# BinaryClockDisplay.net
KiCad netlist of a schematic drawn in EAGLE
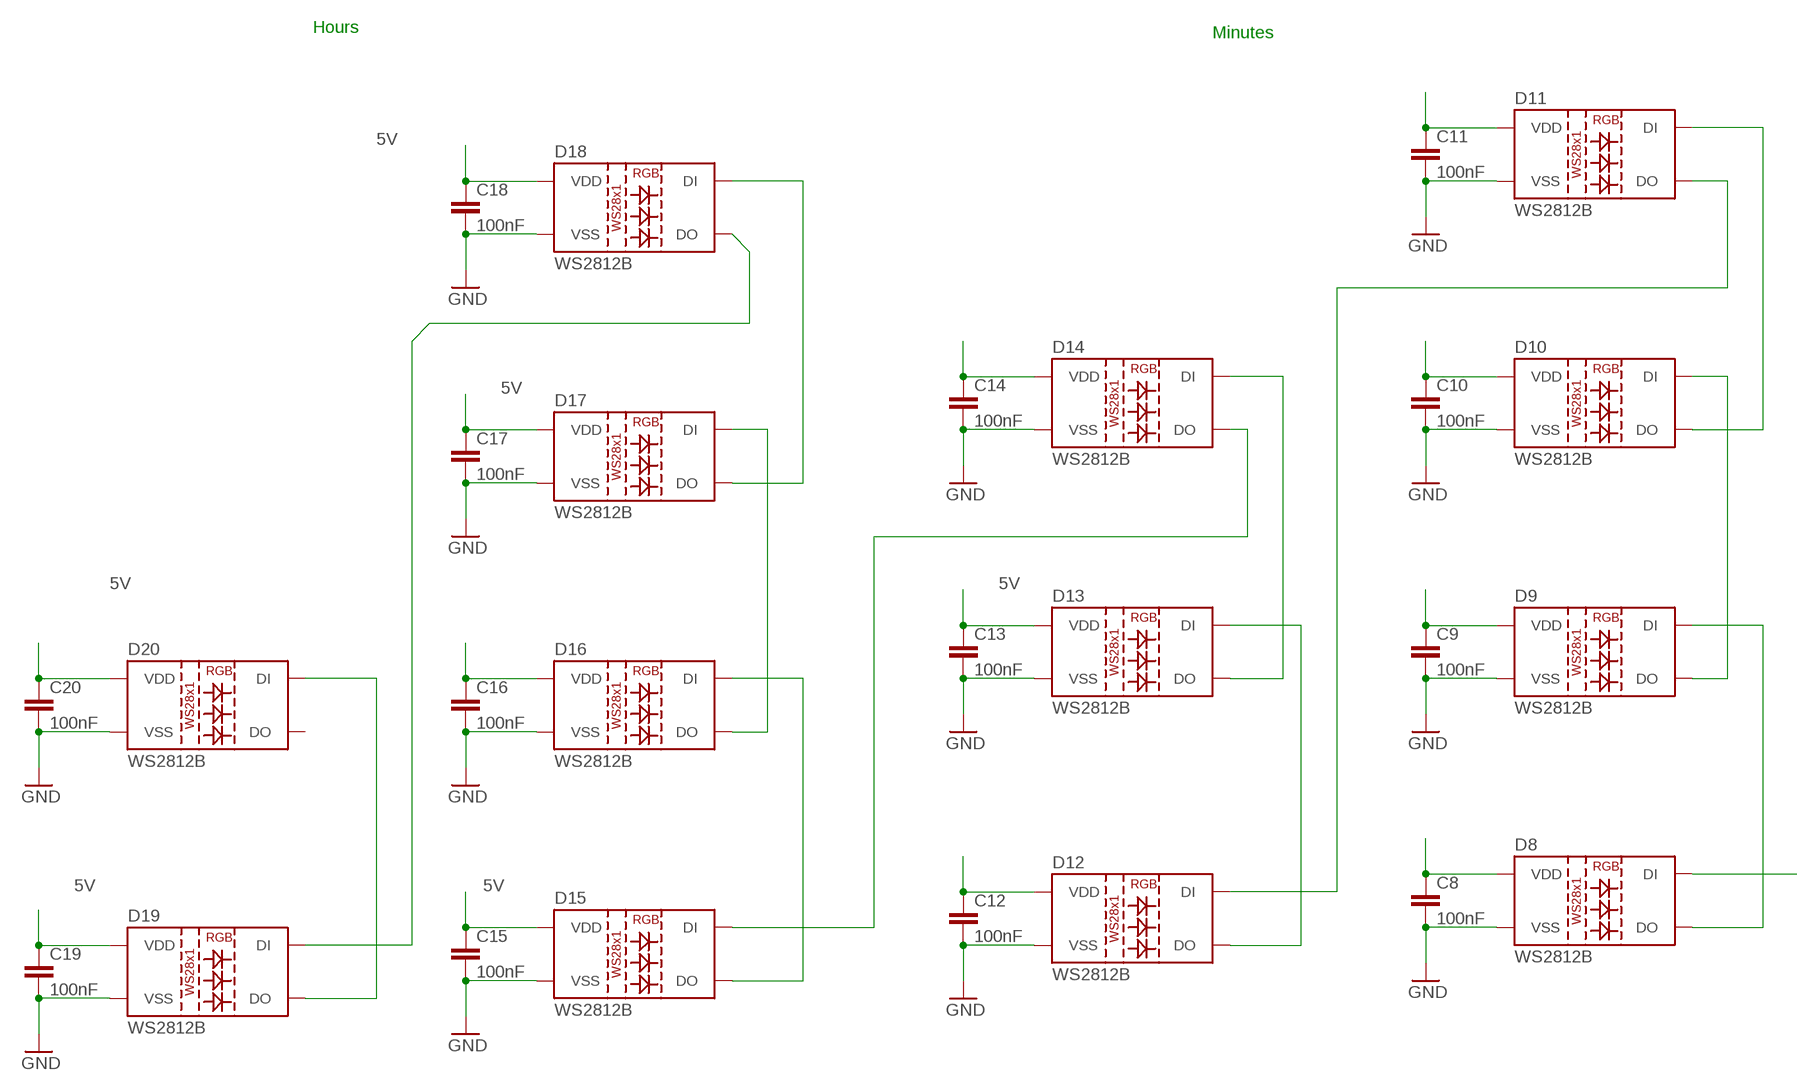
[diagram p0: schematic, sheet 1, part 1 of 2]
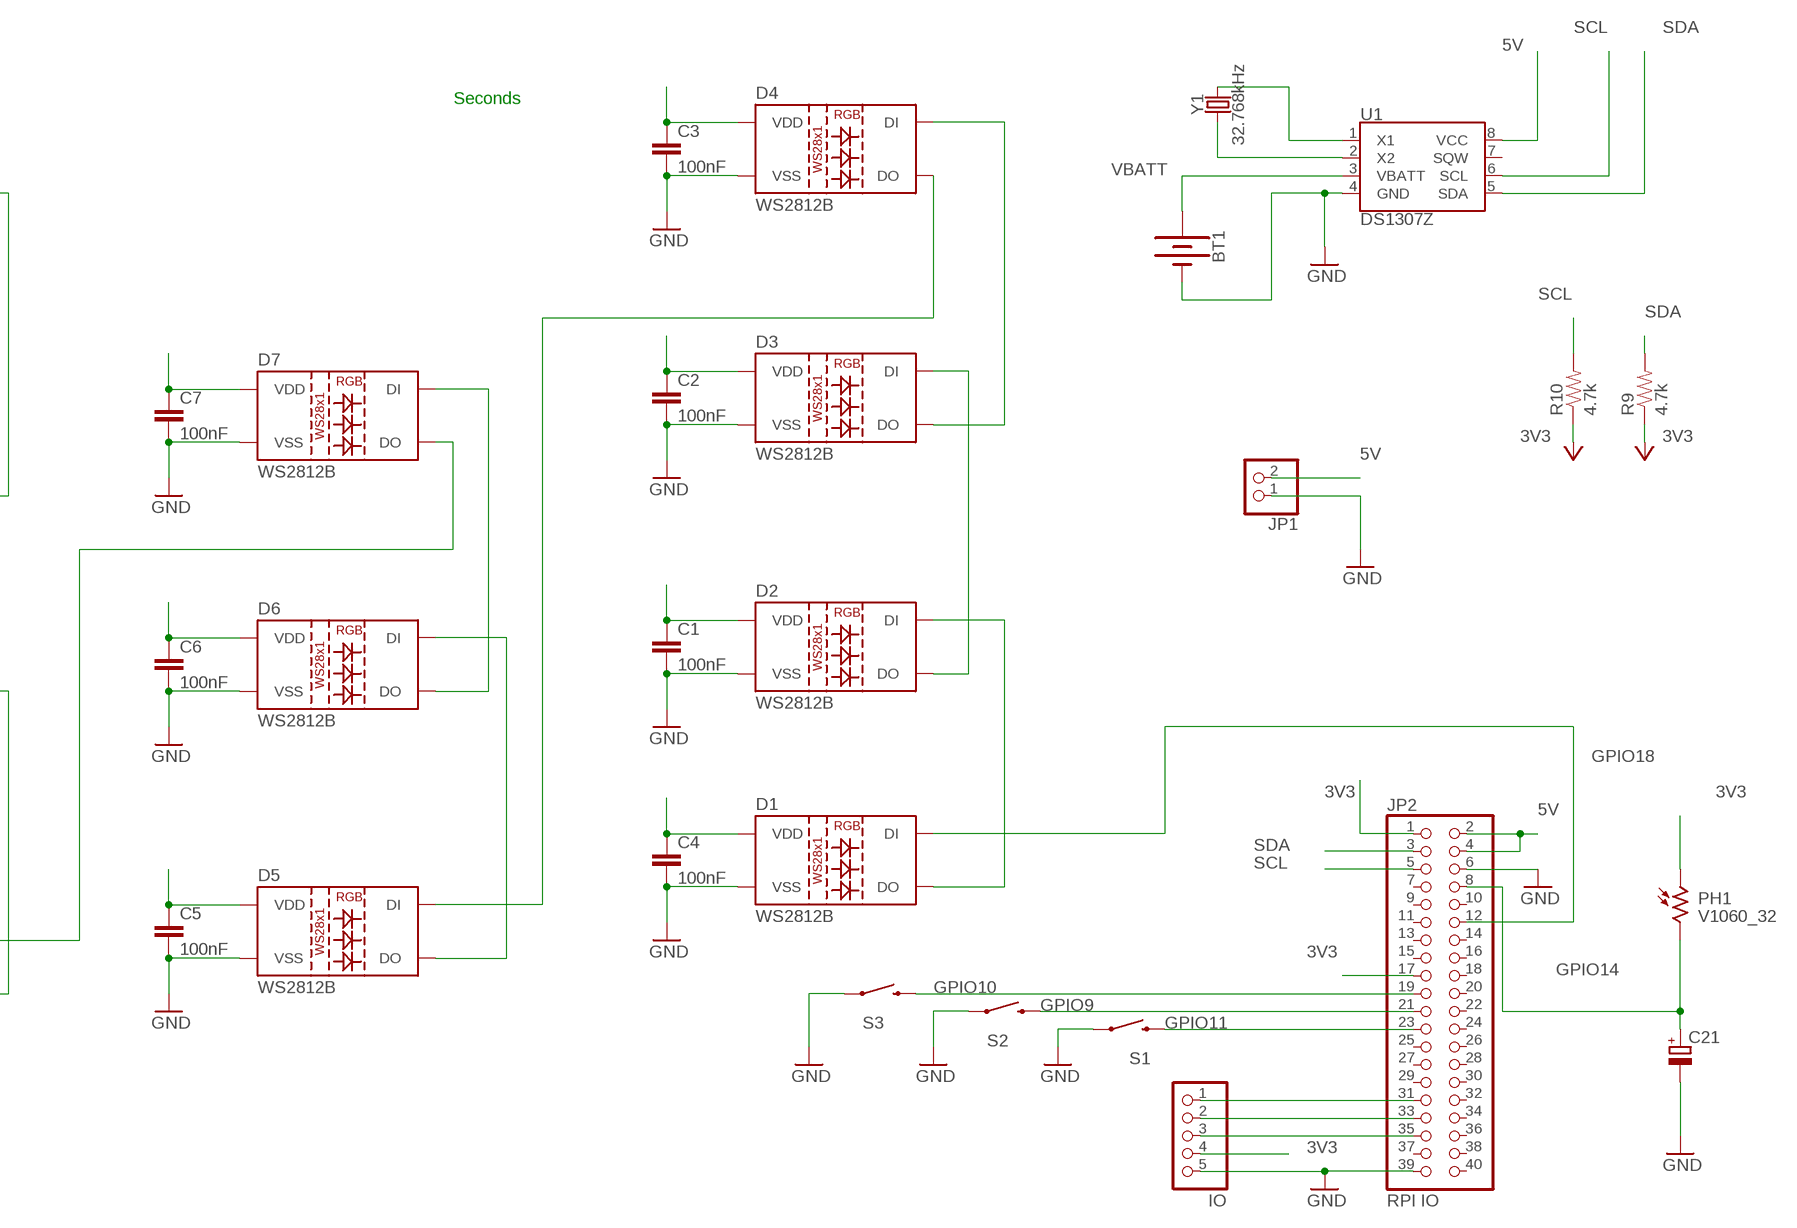
[diagram p1: schematic, sheet 1, part 2 of 2]

(export (version "E")
  (design (tool "Eeschema 10.0.6"))
  (components
    (comp (ref "BT1")
      (value "BATTERY-20MM_PTH")
      (footprint "eagle-import:BATTCOM_20MM_PTH")
      (libsource (lib "eagle-import") (part "BATTERY-20MM_PTH"))
    )
    (comp (ref "C1")
      (value "100nF")
      (footprint "eagle-import:0805")
      (libsource (lib "eagle-import") (part "CAP0805"))
    )
    (comp (ref "C2")
      (value "100nF")
      (footprint "eagle-import:0805")
      (libsource (lib "eagle-import") (part "CAP0805"))
    )
    (comp (ref "C3")
      (value "100nF")
      (footprint "eagle-import:0805")
      (libsource (lib "eagle-import") (part "CAP0805"))
    )
    (comp (ref "C4")
      (value "100nF")
      (footprint "eagle-import:0805")
      (libsource (lib "eagle-import") (part "CAP0805"))
    )
    (comp (ref "C5")
      (value "100nF")
      (footprint "eagle-import:0805")
      (libsource (lib "eagle-import") (part "CAP0805"))
    )
    (comp (ref "C6")
      (value "100nF")
      (footprint "eagle-import:0805")
      (libsource (lib "eagle-import") (part "CAP0805"))
    )
    (comp (ref "C7")
      (value "100nF")
      (footprint "eagle-import:0805")
      (libsource (lib "eagle-import") (part "CAP0805"))
    )
    (comp (ref "C8")
      (value "100nF")
      (footprint "eagle-import:0805")
      (libsource (lib "eagle-import") (part "CAP0805"))
    )
    (comp (ref "C9")
      (value "100nF")
      (footprint "eagle-import:0805")
      (libsource (lib "eagle-import") (part "CAP0805"))
    )
    (comp (ref "C10")
      (value "100nF")
      (footprint "eagle-import:0805")
      (libsource (lib "eagle-import") (part "CAP0805"))
    )
    (comp (ref "C11")
      (value "100nF")
      (footprint "eagle-import:0805")
      (libsource (lib "eagle-import") (part "CAP0805"))
    )
    (comp (ref "C12")
      (value "100nF")
      (footprint "eagle-import:0805")
      (libsource (lib "eagle-import") (part "CAP0805"))
    )
    (comp (ref "C13")
      (value "100nF")
      (footprint "eagle-import:0805")
      (libsource (lib "eagle-import") (part "CAP0805"))
    )
    (comp (ref "C14")
      (value "100nF")
      (footprint "eagle-import:0805")
      (libsource (lib "eagle-import") (part "CAP0805"))
    )
    (comp (ref "C15")
      (value "100nF")
      (footprint "eagle-import:0805")
      (libsource (lib "eagle-import") (part "CAP0805"))
    )
    (comp (ref "C16")
      (value "100nF")
      (footprint "eagle-import:0805")
      (libsource (lib "eagle-import") (part "CAP0805"))
    )
    (comp (ref "C17")
      (value "100nF")
      (footprint "eagle-import:0805")
      (libsource (lib "eagle-import") (part "CAP0805"))
    )
    (comp (ref "C18")
      (value "100nF")
      (footprint "eagle-import:0805")
      (libsource (lib "eagle-import") (part "CAP0805"))
    )
    (comp (ref "C19")
      (value "100nF")
      (footprint "eagle-import:0805")
      (libsource (lib "eagle-import") (part "CAP0805"))
    )
    (comp (ref "C20")
      (value "100nF")
      (footprint "eagle-import:0805")
      (libsource (lib "eagle-import") (part "CAP0805"))
    )
    (comp (ref "C21")
      (value "CPOL-EUE5-10.5")
      (footprint "eagle-import:E5-10,5")
      (libsource (lib "eagle-import") (part "CPOL-EUE5-10.5"))
    )
    (comp (ref "D1")
      (value "WS2812B")
      (footprint "eagle-import:WS2812B")
      (libsource (lib "eagle-import") (part "WS2812B"))
    )
    (comp (ref "D2")
      (value "WS2812B")
      (footprint "eagle-import:WS2812B")
      (libsource (lib "eagle-import") (part "WS2812B"))
    )
    (comp (ref "D3")
      (value "WS2812B")
      (footprint "eagle-import:WS2812B")
      (libsource (lib "eagle-import") (part "WS2812B"))
    )
    (comp (ref "D4")
      (value "WS2812B")
      (footprint "eagle-import:WS2812B")
      (libsource (lib "eagle-import") (part "WS2812B"))
    )
    (comp (ref "D5")
      (value "WS2812B")
      (footprint "eagle-import:WS2812B")
      (libsource (lib "eagle-import") (part "WS2812B"))
    )
    (comp (ref "D6")
      (value "WS2812B")
      (footprint "eagle-import:WS2812B")
      (libsource (lib "eagle-import") (part "WS2812B"))
    )
    (comp (ref "D7")
      (value "WS2812B")
      (footprint "eagle-import:WS2812B")
      (libsource (lib "eagle-import") (part "WS2812B"))
    )
    (comp (ref "D8")
      (value "WS2812B")
      (footprint "eagle-import:WS2812B")
      (libsource (lib "eagle-import") (part "WS2812B"))
    )
    (comp (ref "D9")
      (value "WS2812B")
      (footprint "eagle-import:WS2812B")
      (libsource (lib "eagle-import") (part "WS2812B"))
    )
    (comp (ref "D10")
      (value "WS2812B")
      (footprint "eagle-import:WS2812B")
      (libsource (lib "eagle-import") (part "WS2812B"))
    )
    (comp (ref "D11")
      (value "WS2812B")
      (footprint "eagle-import:WS2812B")
      (libsource (lib "eagle-import") (part "WS2812B"))
    )
    (comp (ref "D12")
      (value "WS2812B")
      (footprint "eagle-import:WS2812B")
      (libsource (lib "eagle-import") (part "WS2812B"))
    )
    (comp (ref "D13")
      (value "WS2812B")
      (footprint "eagle-import:WS2812B")
      (libsource (lib "eagle-import") (part "WS2812B"))
    )
    (comp (ref "D14")
      (value "WS2812B")
      (footprint "eagle-import:WS2812B")
      (libsource (lib "eagle-import") (part "WS2812B"))
    )
    (comp (ref "D15")
      (value "WS2812B")
      (footprint "eagle-import:WS2812B")
      (libsource (lib "eagle-import") (part "WS2812B"))
    )
    (comp (ref "D16")
      (value "WS2812B")
      (footprint "eagle-import:WS2812B")
      (libsource (lib "eagle-import") (part "WS2812B"))
    )
    (comp (ref "D17")
      (value "WS2812B")
      (footprint "eagle-import:WS2812B")
      (libsource (lib "eagle-import") (part "WS2812B"))
    )
    (comp (ref "D18")
      (value "WS2812B")
      (footprint "eagle-import:WS2812B")
      (libsource (lib "eagle-import") (part "WS2812B"))
    )
    (comp (ref "D19")
      (value "WS2812B")
      (footprint "eagle-import:WS2812B")
      (libsource (lib "eagle-import") (part "WS2812B"))
    )
    (comp (ref "D20")
      (value "WS2812B")
      (footprint "eagle-import:WS2812B")
      (libsource (lib "eagle-import") (part "WS2812B"))
    )
    (comp (ref "JP1")
      (value "PINHD-1X2")
      (footprint "eagle-import:1X02")
      (libsource (lib "eagle-import") (part "PINHD-1X2"))
    )
    (comp (ref "JP2")
      (value "RPI IO")
      (footprint "eagle-import:2X20")
      (libsource (lib "eagle-import") (part "PINHD-2X20"))
    )
    (comp (ref "JP4")
      (value "IO")
      (footprint "eagle-import:1X05")
      (libsource (lib "eagle-import") (part "PINHD-1X5"))
    )
    (comp (ref "PH1")
      (value "V1060_32")
      (footprint "eagle-import:TO-5_V10")
      (libsource (lib "eagle-import") (part "?1060V_32"))
    )
    (comp (ref "R9")
      (value "4.7k")
      (footprint "eagle-import:0805")
      (libsource (lib "eagle-import") (part "RESISTOR0805-RES"))
    )
    (comp (ref "R10")
      (value "4.7k")
      (footprint "eagle-import:0805")
      (libsource (lib "eagle-import") (part "RESISTOR0805-RES"))
    )
    (comp (ref "S1")
      (value "SWITCH")
      (footprint "eagle-import:TACTILE-SWITCH-1101NE")
      (libsource (lib "eagle-import") (part "SWITCH-MOMENTARY-2SMD-1101NE"))
    )
    (comp (ref "S2")
      (value "SWITCH")
      (footprint "eagle-import:TACTILE-SWITCH-1101NE")
      (libsource (lib "eagle-import") (part "SWITCH-MOMENTARY-2SMD-1101NE"))
    )
    (comp (ref "S3")
      (value "SWITCH")
      (footprint "eagle-import:TACTILE-SWITCH-1101NE")
      (libsource (lib "eagle-import") (part "SWITCH-MOMENTARY-2SMD-1101NE"))
    )
    (comp (ref "U1")
      (value "DS1307Z")
      (footprint "eagle-import:SO08-0.15")
      (libsource (lib "eagle-import") (part "DS1307Z"))
    )
    (comp (ref "Y1")
      (value "32.768kHz")
      (footprint "eagle-import:CRYSTAL-PTH-2X6-CYL")
      (libsource (lib "eagle-import") (part "CRYSTAL-32.768KHZPTH-2X6"))
    )
  )
  (nets
    (net (code "1") (name "+3V3") (class "Default")
      (node (ref "JP2") (pin "1") (pinfunction "1_1") (pintype "passive"))
      (node (ref "JP2") (pin "17") (pinfunction "17_17") (pintype "passive"))
      (node (ref "JP4") (pin "4") (pinfunction "4_4") (pintype "passive"))
      (node (ref "PH1") (pin "1") (pinfunction "1_1") (pintype "passive"))
      (node (ref "R10") (pin "1") (pinfunction "1_1") (pintype "passive"))
      (node (ref "R9") (pin "1") (pinfunction "1_1") (pintype "passive"))
    )
    (net (code "2") (name "/5V") (class "Default")
      (node (ref "C1") (pin "1") (pinfunction "1_1") (pintype "passive"))
      (node (ref "C10") (pin "1") (pinfunction "1_1") (pintype "passive"))
      (node (ref "C11") (pin "1") (pinfunction "1_1") (pintype "passive"))
      (node (ref "C12") (pin "1") (pinfunction "1_1") (pintype "passive"))
      (node (ref "C13") (pin "1") (pinfunction "1_1") (pintype "passive"))
      (node (ref "C14") (pin "1") (pinfunction "1_1") (pintype "passive"))
      (node (ref "C15") (pin "1") (pinfunction "1_1") (pintype "passive"))
      (node (ref "C16") (pin "1") (pinfunction "1_1") (pintype "passive"))
      (node (ref "C17") (pin "1") (pinfunction "1_1") (pintype "passive"))
      (node (ref "C18") (pin "1") (pinfunction "1_1") (pintype "passive"))
      (node (ref "C19") (pin "1") (pinfunction "1_1") (pintype "passive"))
      (node (ref "C2") (pin "1") (pinfunction "1_1") (pintype "passive"))
      (node (ref "C20") (pin "1") (pinfunction "1_1") (pintype "passive"))
      (node (ref "C3") (pin "1") (pinfunction "1_1") (pintype "passive"))
      (node (ref "C4") (pin "1") (pinfunction "1_1") (pintype "passive"))
      (node (ref "C5") (pin "1") (pinfunction "1_1") (pintype "passive"))
      (node (ref "C6") (pin "1") (pinfunction "1_1") (pintype "passive"))
      (node (ref "C7") (pin "1") (pinfunction "1_1") (pintype "passive"))
      (node (ref "C8") (pin "1") (pinfunction "1_1") (pintype "passive"))
      (node (ref "C9") (pin "1") (pinfunction "1_1") (pintype "passive"))
      (node (ref "D1") (pin "1") (pinfunction "VDD_1") (pintype "bidirectional"))
      (node (ref "D10") (pin "1") (pinfunction "VDD_1") (pintype "bidirectional"))
      (node (ref "D11") (pin "1") (pinfunction "VDD_1") (pintype "bidirectional"))
      (node (ref "D12") (pin "1") (pinfunction "VDD_1") (pintype "bidirectional"))
      (node (ref "D13") (pin "1") (pinfunction "VDD_1") (pintype "bidirectional"))
      (node (ref "D14") (pin "1") (pinfunction "VDD_1") (pintype "bidirectional"))
      (node (ref "D15") (pin "1") (pinfunction "VDD_1") (pintype "bidirectional"))
      (node (ref "D16") (pin "1") (pinfunction "VDD_1") (pintype "bidirectional"))
      (node (ref "D17") (pin "1") (pinfunction "VDD_1") (pintype "bidirectional"))
      (node (ref "D18") (pin "1") (pinfunction "VDD_1") (pintype "bidirectional"))
      (node (ref "D19") (pin "1") (pinfunction "VDD_1") (pintype "bidirectional"))
      (node (ref "D2") (pin "1") (pinfunction "VDD_1") (pintype "bidirectional"))
      (node (ref "D20") (pin "1") (pinfunction "VDD_1") (pintype "bidirectional"))
      (node (ref "D3") (pin "1") (pinfunction "VDD_1") (pintype "bidirectional"))
      (node (ref "D4") (pin "1") (pinfunction "VDD_1") (pintype "bidirectional"))
      (node (ref "D5") (pin "1") (pinfunction "VDD_1") (pintype "bidirectional"))
      (node (ref "D6") (pin "1") (pinfunction "VDD_1") (pintype "bidirectional"))
      (node (ref "D7") (pin "1") (pinfunction "VDD_1") (pintype "bidirectional"))
      (node (ref "D8") (pin "1") (pinfunction "VDD_1") (pintype "bidirectional"))
      (node (ref "D9") (pin "1") (pinfunction "VDD_1") (pintype "bidirectional"))
      (node (ref "JP1") (pin "2") (pinfunction "2_2") (pintype "passive"))
      (node (ref "JP2") (pin "2") (pinfunction "2_2") (pintype "passive"))
      (node (ref "JP2") (pin "4") (pinfunction "4_4") (pintype "passive"))
      (node (ref "U1") (pin "8") (pinfunction "VCC_8") (pintype "bidirectional"))
    )
    (net (code "3") (name "/GPIO9") (class "Default")
      (node (ref "JP2") (pin "21") (pinfunction "21_21") (pintype "passive"))
      (node (ref "S2") (pin "2") (pinfunction "2_2") (pintype "passive"))
    )
    (net (code "4") (name "/GPIO10") (class "Default")
      (node (ref "JP2") (pin "19") (pinfunction "19_19") (pintype "passive"))
      (node (ref "S3") (pin "2") (pinfunction "2_2") (pintype "passive"))
    )
    (net (code "5") (name "/GPIO11") (class "Default")
      (node (ref "JP2") (pin "23") (pinfunction "23_23") (pintype "passive"))
      (node (ref "S1") (pin "2") (pinfunction "2_2") (pintype "passive"))
    )
    (net (code "6") (name "/GPIO14") (class "Default")
      (node (ref "C21") (pin "+") (pinfunction "+_+") (pintype "passive"))
      (node (ref "JP2") (pin "8") (pinfunction "8_8") (pintype "passive"))
      (node (ref "PH1") (pin "2") (pinfunction "2_2") (pintype "passive"))
    )
    (net (code "7") (name "/GPIO18") (class "Default")
      (node (ref "D1") (pin "4") (pinfunction "DI_4") (pintype "bidirectional"))
      (node (ref "JP2") (pin "12") (pinfunction "12_12") (pintype "passive"))
    )
    (net (code "8") (name "/SCL") (class "Default")
      (node (ref "JP2") (pin "5") (pinfunction "5_5") (pintype "passive"))
      (node (ref "R10") (pin "2") (pinfunction "2_2") (pintype "passive"))
      (node (ref "U1") (pin "6") (pinfunction "SCL_6") (pintype "bidirectional"))
    )
    (net (code "9") (name "/SDA") (class "Default")
      (node (ref "JP2") (pin "3") (pinfunction "3_3") (pintype "passive"))
      (node (ref "R9") (pin "2") (pinfunction "2_2") (pintype "passive"))
      (node (ref "U1") (pin "5") (pinfunction "SDA_5") (pintype "bidirectional"))
    )
    (net (code "10") (name "/VBATT") (class "Default")
      (node (ref "BT1") (pin "1") (pinfunction "+_1") (pintype "power_in"))
      (node (ref "U1") (pin "3") (pinfunction "VBATT_3") (pintype "bidirectional"))
    )
    (net (code "11") (name "GND") (class "Default")
      (node (ref "BT1") (pin "2") (pinfunction "-_2") (pintype "power_in"))
      (node (ref "C1") (pin "2") (pinfunction "2_2") (pintype "passive"))
      (node (ref "C10") (pin "2") (pinfunction "2_2") (pintype "passive"))
      (node (ref "C11") (pin "2") (pinfunction "2_2") (pintype "passive"))
      (node (ref "C12") (pin "2") (pinfunction "2_2") (pintype "passive"))
      (node (ref "C13") (pin "2") (pinfunction "2_2") (pintype "passive"))
      (node (ref "C14") (pin "2") (pinfunction "2_2") (pintype "passive"))
      (node (ref "C15") (pin "2") (pinfunction "2_2") (pintype "passive"))
      (node (ref "C16") (pin "2") (pinfunction "2_2") (pintype "passive"))
      (node (ref "C17") (pin "2") (pinfunction "2_2") (pintype "passive"))
      (node (ref "C18") (pin "2") (pinfunction "2_2") (pintype "passive"))
      (node (ref "C19") (pin "2") (pinfunction "2_2") (pintype "passive"))
      (node (ref "C2") (pin "2") (pinfunction "2_2") (pintype "passive"))
      (node (ref "C20") (pin "2") (pinfunction "2_2") (pintype "passive"))
      (node (ref "C21") (pin "-") (pinfunction "-_-") (pintype "passive"))
      (node (ref "C3") (pin "2") (pinfunction "2_2") (pintype "passive"))
      (node (ref "C4") (pin "2") (pinfunction "2_2") (pintype "passive"))
      (node (ref "C5") (pin "2") (pinfunction "2_2") (pintype "passive"))
      (node (ref "C6") (pin "2") (pinfunction "2_2") (pintype "passive"))
      (node (ref "C7") (pin "2") (pinfunction "2_2") (pintype "passive"))
      (node (ref "C8") (pin "2") (pinfunction "2_2") (pintype "passive"))
      (node (ref "C9") (pin "2") (pinfunction "2_2") (pintype "passive"))
      (node (ref "D1") (pin "3") (pinfunction "VSS_3") (pintype "bidirectional"))
      (node (ref "D10") (pin "3") (pinfunction "VSS_3") (pintype "bidirectional"))
      (node (ref "D11") (pin "3") (pinfunction "VSS_3") (pintype "bidirectional"))
      (node (ref "D12") (pin "3") (pinfunction "VSS_3") (pintype "bidirectional"))
      (node (ref "D13") (pin "3") (pinfunction "VSS_3") (pintype "bidirectional"))
      (node (ref "D14") (pin "3") (pinfunction "VSS_3") (pintype "bidirectional"))
      (node (ref "D15") (pin "3") (pinfunction "VSS_3") (pintype "bidirectional"))
      (node (ref "D16") (pin "3") (pinfunction "VSS_3") (pintype "bidirectional"))
      (node (ref "D17") (pin "3") (pinfunction "VSS_3") (pintype "bidirectional"))
      (node (ref "D18") (pin "3") (pinfunction "VSS_3") (pintype "bidirectional"))
      (node (ref "D19") (pin "3") (pinfunction "VSS_3") (pintype "bidirectional"))
      (node (ref "D2") (pin "3") (pinfunction "VSS_3") (pintype "bidirectional"))
      (node (ref "D20") (pin "3") (pinfunction "VSS_3") (pintype "bidirectional"))
      (node (ref "D3") (pin "3") (pinfunction "VSS_3") (pintype "bidirectional"))
      (node (ref "D4") (pin "3") (pinfunction "VSS_3") (pintype "bidirectional"))
      (node (ref "D5") (pin "3") (pinfunction "VSS_3") (pintype "bidirectional"))
      (node (ref "D6") (pin "3") (pinfunction "VSS_3") (pintype "bidirectional"))
      (node (ref "D7") (pin "3") (pinfunction "VSS_3") (pintype "bidirectional"))
      (node (ref "D8") (pin "3") (pinfunction "VSS_3") (pintype "bidirectional"))
      (node (ref "D9") (pin "3") (pinfunction "VSS_3") (pintype "bidirectional"))
      (node (ref "JP1") (pin "1") (pinfunction "1_1") (pintype "passive"))
      (node (ref "JP2") (pin "39") (pinfunction "39_39") (pintype "passive"))
      (node (ref "JP2") (pin "6") (pinfunction "6_6") (pintype "passive"))
      (node (ref "JP4") (pin "5") (pinfunction "5_5") (pintype "passive"))
      (node (ref "S1") (pin "1") (pinfunction "1_1") (pintype "passive"))
      (node (ref "S2") (pin "1") (pinfunction "1_1") (pintype "passive"))
      (node (ref "S3") (pin "1") (pinfunction "1_1") (pintype "passive"))
      (node (ref "U1") (pin "4") (pinfunction "GND_4") (pintype "bidirectional"))
    )
    (net (code "12") (name "Net-(D1-DO)") (class "Default")
      (node (ref "D1") (pin "2") (pinfunction "DO_2") (pintype "bidirectional"))
      (node (ref "D2") (pin "4") (pinfunction "DI_4") (pintype "bidirectional"))
    )
    (net (code "13") (name "Net-(D2-DO)") (class "Default")
      (node (ref "D2") (pin "2") (pinfunction "DO_2") (pintype "bidirectional"))
      (node (ref "D3") (pin "4") (pinfunction "DI_4") (pintype "bidirectional"))
    )
    (net (code "14") (name "Net-(D3-DO)") (class "Default")
      (node (ref "D3") (pin "2") (pinfunction "DO_2") (pintype "bidirectional"))
      (node (ref "D4") (pin "4") (pinfunction "DI_4") (pintype "bidirectional"))
    )
    (net (code "15") (name "Net-(D4-DO)") (class "Default")
      (node (ref "D4") (pin "2") (pinfunction "DO_2") (pintype "bidirectional"))
      (node (ref "D5") (pin "4") (pinfunction "DI_4") (pintype "bidirectional"))
    )
    (net (code "16") (name "Net-(D5-DO)") (class "Default")
      (node (ref "D5") (pin "2") (pinfunction "DO_2") (pintype "bidirectional"))
      (node (ref "D6") (pin "4") (pinfunction "DI_4") (pintype "bidirectional"))
    )
    (net (code "17") (name "Net-(D6-DO)") (class "Default")
      (node (ref "D6") (pin "2") (pinfunction "DO_2") (pintype "bidirectional"))
      (node (ref "D7") (pin "4") (pinfunction "DI_4") (pintype "bidirectional"))
    )
    (net (code "18") (name "Net-(D7-DO)") (class "Default")
      (node (ref "D7") (pin "2") (pinfunction "DO_2") (pintype "bidirectional"))
      (node (ref "D8") (pin "4") (pinfunction "DI_4") (pintype "bidirectional"))
    )
    (net (code "19") (name "Net-(D8-DO)") (class "Default")
      (node (ref "D8") (pin "2") (pinfunction "DO_2") (pintype "bidirectional"))
      (node (ref "D9") (pin "4") (pinfunction "DI_4") (pintype "bidirectional"))
    )
    (net (code "20") (name "Net-(D10-DI)") (class "Default")
      (node (ref "D10") (pin "4") (pinfunction "DI_4") (pintype "bidirectional"))
      (node (ref "D9") (pin "2") (pinfunction "DO_2") (pintype "bidirectional"))
    )
    (net (code "21") (name "Net-(D10-DO)") (class "Default")
      (node (ref "D10") (pin "2") (pinfunction "DO_2") (pintype "bidirectional"))
      (node (ref "D11") (pin "4") (pinfunction "DI_4") (pintype "bidirectional"))
    )
    (net (code "22") (name "Net-(D11-DO)") (class "Default")
      (node (ref "D11") (pin "2") (pinfunction "DO_2") (pintype "bidirectional"))
      (node (ref "D12") (pin "4") (pinfunction "DI_4") (pintype "bidirectional"))
    )
    (net (code "23") (name "Net-(D12-DO)") (class "Default")
      (node (ref "D12") (pin "2") (pinfunction "DO_2") (pintype "bidirectional"))
      (node (ref "D13") (pin "4") (pinfunction "DI_4") (pintype "bidirectional"))
    )
    (net (code "24") (name "Net-(D13-DO)") (class "Default")
      (node (ref "D13") (pin "2") (pinfunction "DO_2") (pintype "bidirectional"))
      (node (ref "D14") (pin "4") (pinfunction "DI_4") (pintype "bidirectional"))
    )
    (net (code "25") (name "Net-(D14-DO)") (class "Default")
      (node (ref "D14") (pin "2") (pinfunction "DO_2") (pintype "bidirectional"))
      (node (ref "D15") (pin "4") (pinfunction "DI_4") (pintype "bidirectional"))
    )
    (net (code "26") (name "Net-(D15-DO)") (class "Default")
      (node (ref "D15") (pin "2") (pinfunction "DO_2") (pintype "bidirectional"))
      (node (ref "D16") (pin "4") (pinfunction "DI_4") (pintype "bidirectional"))
    )
    (net (code "27") (name "Net-(D16-DO)") (class "Default")
      (node (ref "D16") (pin "2") (pinfunction "DO_2") (pintype "bidirectional"))
      (node (ref "D17") (pin "4") (pinfunction "DI_4") (pintype "bidirectional"))
    )
    (net (code "28") (name "Net-(D17-DO)") (class "Default")
      (node (ref "D17") (pin "2") (pinfunction "DO_2") (pintype "bidirectional"))
      (node (ref "D18") (pin "4") (pinfunction "DI_4") (pintype "bidirectional"))
    )
    (net (code "29") (name "Net-(D18-DO)") (class "Default")
      (node (ref "D18") (pin "2") (pinfunction "DO_2") (pintype "bidirectional"))
      (node (ref "D19") (pin "4") (pinfunction "DI_4") (pintype "bidirectional"))
    )
    (net (code "30") (name "Net-(D19-DO)") (class "Default")
      (node (ref "D19") (pin "2") (pinfunction "DO_2") (pintype "bidirectional"))
      (node (ref "D20") (pin "4") (pinfunction "DI_4") (pintype "bidirectional"))
    )
    (net (code "31") (name "Net-(JP2-Pad31)") (class "Default")
      (node (ref "JP2") (pin "31") (pinfunction "31_31") (pintype "passive"))
      (node (ref "JP4") (pin "1") (pinfunction "1_1") (pintype "passive"))
    )
    (net (code "32") (name "Net-(JP2-Pad33)") (class "Default")
      (node (ref "JP2") (pin "33") (pinfunction "33_33") (pintype "passive"))
      (node (ref "JP4") (pin "2") (pinfunction "2_2") (pintype "passive"))
    )
    (net (code "33") (name "Net-(JP2-Pad35)") (class "Default")
      (node (ref "JP2") (pin "35") (pinfunction "35_35") (pintype "passive"))
      (node (ref "JP4") (pin "3") (pinfunction "3_3") (pintype "passive"))
    )
    (net (code "34") (name "Net-(U1-X1)") (class "Default")
      (node (ref "U1") (pin "1") (pinfunction "X1_1") (pintype "bidirectional"))
      (node (ref "Y1") (pin "2") (pinfunction "2_2") (pintype "passive"))
    )
    (net (code "35") (name "Net-(U1-X2)") (class "Default")
      (node (ref "U1") (pin "2") (pinfunction "X2_2") (pintype "bidirectional"))
      (node (ref "Y1") (pin "1") (pinfunction "1_1") (pintype "passive"))
    )
    (net (code "36") (name "unconnected-(D20-DO-Pad2)") (class "Default")
      (node (ref "D20") (pin "2") (pinfunction "DO_2") (pintype "bidirectional"))
    )
    (net (code "37") (name "unconnected-(JP2-Pad7)") (class "Default")
      (node (ref "JP2") (pin "7") (pinfunction "7_7") (pintype "passive"))
    )
    (net (code "38") (name "unconnected-(JP2-Pad9)") (class "Default")
      (node (ref "JP2") (pin "9") (pinfunction "9_9") (pintype "passive"))
    )
    (net (code "39") (name "unconnected-(JP2-Pad10)") (class "Default")
      (node (ref "JP2") (pin "10") (pinfunction "10_10") (pintype "passive"))
    )
    (net (code "40") (name "unconnected-(JP2-Pad11)") (class "Default")
      (node (ref "JP2") (pin "11") (pinfunction "11_11") (pintype "passive"))
    )
    (net (code "41") (name "unconnected-(JP2-Pad13)") (class "Default")
      (node (ref "JP2") (pin "13") (pinfunction "13_13") (pintype "passive"))
    )
    (net (code "42") (name "unconnected-(JP2-Pad14)") (class "Default")
      (node (ref "JP2") (pin "14") (pinfunction "14_14") (pintype "passive"))
    )
    (net (code "43") (name "unconnected-(JP2-Pad15)") (class "Default")
      (node (ref "JP2") (pin "15") (pinfunction "15_15") (pintype "passive"))
    )
    (net (code "44") (name "unconnected-(JP2-Pad16)") (class "Default")
      (node (ref "JP2") (pin "16") (pinfunction "16_16") (pintype "passive"))
    )
    (net (code "45") (name "unconnected-(JP2-Pad18)") (class "Default")
      (node (ref "JP2") (pin "18") (pinfunction "18_18") (pintype "passive"))
    )
    (net (code "46") (name "unconnected-(JP2-Pad20)") (class "Default")
      (node (ref "JP2") (pin "20") (pinfunction "20_20") (pintype "passive"))
    )
    (net (code "47") (name "unconnected-(JP2-Pad22)") (class "Default")
      (node (ref "JP2") (pin "22") (pinfunction "22_22") (pintype "passive"))
    )
    (net (code "48") (name "unconnected-(JP2-Pad24)") (class "Default")
      (node (ref "JP2") (pin "24") (pinfunction "24_24") (pintype "passive"))
    )
    (net (code "49") (name "unconnected-(JP2-Pad25)") (class "Default")
      (node (ref "JP2") (pin "25") (pinfunction "25_25") (pintype "passive"))
    )
    (net (code "50") (name "unconnected-(JP2-Pad26)") (class "Default")
      (node (ref "JP2") (pin "26") (pinfunction "26_26") (pintype "passive"))
    )
    (net (code "51") (name "unconnected-(JP2-Pad27)") (class "Default")
      (node (ref "JP2") (pin "27") (pinfunction "27_27") (pintype "passive"))
    )
    (net (code "52") (name "unconnected-(JP2-Pad28)") (class "Default")
      (node (ref "JP2") (pin "28") (pinfunction "28_28") (pintype "passive"))
    )
    (net (code "53") (name "unconnected-(JP2-Pad29)") (class "Default")
      (node (ref "JP2") (pin "29") (pinfunction "29_29") (pintype "passive"))
    )
    (net (code "54") (name "unconnected-(JP2-Pad30)") (class "Default")
      (node (ref "JP2") (pin "30") (pinfunction "30_30") (pintype "passive"))
    )
    (net (code "55") (name "unconnected-(JP2-Pad32)") (class "Default")
      (node (ref "JP2") (pin "32") (pinfunction "32_32") (pintype "passive"))
    )
    (net (code "56") (name "unconnected-(JP2-Pad34)") (class "Default")
      (node (ref "JP2") (pin "34") (pinfunction "34_34") (pintype "passive"))
    )
    (net (code "57") (name "unconnected-(JP2-Pad36)") (class "Default")
      (node (ref "JP2") (pin "36") (pinfunction "36_36") (pintype "passive"))
    )
    (net (code "58") (name "unconnected-(JP2-Pad37)") (class "Default")
      (node (ref "JP2") (pin "37") (pinfunction "37_37") (pintype "passive"))
    )
    (net (code "59") (name "unconnected-(JP2-Pad38)") (class "Default")
      (node (ref "JP2") (pin "38") (pinfunction "38_38") (pintype "passive"))
    )
    (net (code "60") (name "unconnected-(JP2-Pad40)") (class "Default")
      (node (ref "JP2") (pin "40") (pinfunction "40_40") (pintype "passive"))
    )
    (net (code "61") (name "unconnected-(U1-SQW-Pad7)") (class "Default")
      (node (ref "U1") (pin "7") (pinfunction "SQW_7") (pintype "bidirectional"))
    )
  )
)
